# MCU.net
KiCad netlist of a schematic drawn in Altium Designer
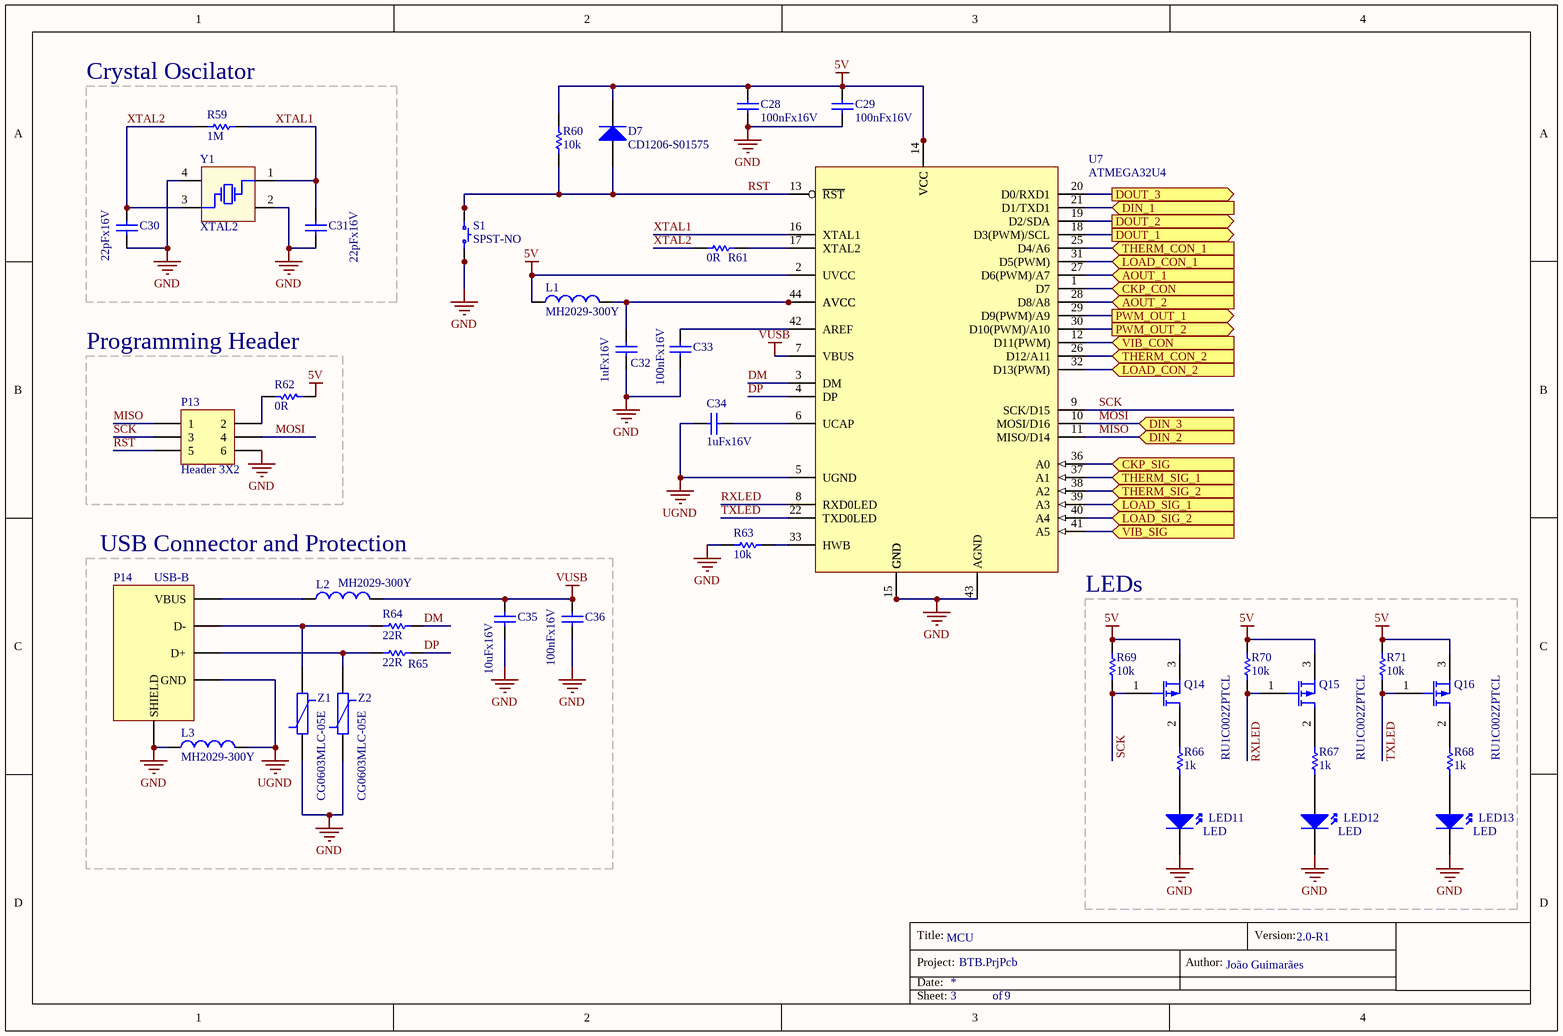
[diagram p0: MCU.SchDoc]

(export (version "E")
  (design (tool "Eeschema 10.0.6"))
  (components
    (comp (ref "C28")
      (value "100nFx16V")
      (footprint "DISC-0805")
      (description "Capacitor")
      (libsource (lib "IntLib") (part "Cap"))
    )
    (comp (ref "C29")
      (value "100nFx16V")
      (footprint "DISC-0805")
      (description "Capacitor")
      (libsource (lib "IntLib") (part "Cap"))
    )
    (comp (ref "C30")
      (value "22pFx16V")
      (footprint "DISC-0805")
      (description "Capacitor")
      (libsource (lib "IntLib") (part "Cap"))
    )
    (comp (ref "C31")
      (value "22pFx16V")
      (footprint "DISC-0805")
      (description "Capacitor")
      (libsource (lib "IntLib") (part "Cap"))
    )
    (comp (ref "C32")
      (value "1uFx16V")
      (footprint "DISC-0805")
      (description "Capacitor")
      (libsource (lib "IntLib") (part "Cap"))
    )
    (comp (ref "C33")
      (value "100nFx16V")
      (footprint "DISC-0805")
      (description "Capacitor")
      (libsource (lib "IntLib") (part "Cap"))
    )
    (comp (ref "C34")
      (value "1uFx16V")
      (footprint "DISC-0805")
      (description "Capacitor")
      (libsource (lib "IntLib") (part "Cap"))
    )
    (comp (ref "C35")
      (value "10uFx16V")
      (footprint "DISC-0805")
      (description "Capacitor")
      (libsource (lib "IntLib") (part "Cap"))
    )
    (comp (ref "C36")
      (value "100nFx16V")
      (footprint "DISC-0805")
      (description "Capacitor")
      (libsource (lib "IntLib") (part "Cap"))
    )
    (comp (ref "D7")
      (value "CD1206-S01575")
      (footprint "DISC-1206")
      (description "Default Diode")
      (fields (field (name "PUBLISHER") "Altium Limited"))
      (libsource (lib "IntLib") (part "Diode"))
    )
    (comp (ref "L1")
      (value "MH2029-300Y")
      (footprint "DISC-0805")
      (description "Chip Inductor")
      (libsource (lib "IntLib") (part "Inductor"))
    )
    (comp (ref "L2")
      (value "MH2029-300Y")
      (footprint "DISC-0805")
      (description "Chip Inductor")
      (libsource (lib "IntLib") (part "Inductor"))
    )
    (comp (ref "L3")
      (value "MH2029-300Y")
      (footprint "DISC-0805")
      (description "Chip Inductor")
      (libsource (lib "IntLib") (part "Inductor"))
    )
    (comp (ref "LED11") (value "LED") (footprint "DISC-LED-0.1-PTH") (libsource (lib "IntLib") (part "LED")))
    (comp (ref "LED12") (value "LED") (footprint "DISC-LED-0.1-PTH") (libsource (lib "IntLib") (part "LED")))
    (comp (ref "LED13") (value "LED") (footprint "DISC-LED-0.1-PTH") (libsource (lib "IntLib") (part "LED")))
    (comp (ref "P13")
      (value "Header 3X2")
      (footprint "CON-HEADER-2X3-PTH")
      (description "Header, 3-Pin, Dual row")
      (fields (field (name "PUBLISHER") "Altium Limited"))
      (libsource (lib "IntLib") (part "Header 3X2"))
    )
    (comp (ref "P14")
      (value "USB-B")
      (footprint "CON-USB-B")
      (description "USB Type-B")
      (libsource (lib "IntLib") (part "USB Type-B"))
    )
    (comp (ref "Q14")
      (value "RU1C002ZPTCL")
      (footprint "DISC-SOT-23")
      (description "P-Channel MOSFET")
      (libsource (lib "IntLib") (part "Transistor-PMOS"))
    )
    (comp (ref "Q15")
      (value "RU1C002ZPTCL")
      (footprint "DISC-SOT-23")
      (description "P-Channel MOSFET")
      (libsource (lib "IntLib") (part "Transistor-PMOS"))
    )
    (comp (ref "Q16")
      (value "RU1C002ZPTCL")
      (footprint "DISC-SOT-23")
      (description "P-Channel MOSFET")
      (libsource (lib "IntLib") (part "Transistor-PMOS"))
    )
    (comp (ref "R59")
      (value "1M")
      (footprint "DISC-0805")
      (description "Resistor")
      (libsource (lib "IntLib") (part "Res"))
    )
    (comp (ref "R60")
      (value "10k")
      (footprint "DISC-0805")
      (description "Resistor")
      (libsource (lib "IntLib") (part "Res"))
    )
    (comp (ref "R61")
      (value "0R")
      (footprint "DISC-0805")
      (description "Resistor")
      (libsource (lib "IntLib") (part "Res"))
    )
    (comp (ref "R62")
      (value "0R")
      (footprint "DISC-0805")
      (description "Resistor")
      (libsource (lib "IntLib") (part "Res"))
    )
    (comp (ref "R63")
      (value "10k")
      (footprint "DISC-0805")
      (description "Resistor")
      (libsource (lib "IntLib") (part "Res"))
    )
    (comp (ref "R64")
      (value "22R")
      (footprint "DISC-0805")
      (description "Resistor")
      (libsource (lib "IntLib") (part "Res"))
    )
    (comp (ref "R65")
      (value "22R")
      (footprint "DISC-0805")
      (description "Resistor")
      (libsource (lib "IntLib") (part "Res"))
    )
    (comp (ref "R66")
      (value "1k")
      (footprint "DISC-0805")
      (description "Resistor")
      (libsource (lib "IntLib") (part "Res"))
    )
    (comp (ref "R67")
      (value "1k")
      (footprint "DISC-0805")
      (description "Resistor")
      (libsource (lib "IntLib") (part "Res"))
    )
    (comp (ref "R68")
      (value "1k")
      (footprint "DISC-0805")
      (description "Resistor")
      (libsource (lib "IntLib") (part "Res"))
    )
    (comp (ref "R69")
      (value "10k")
      (footprint "DISC-0805")
      (description "Resistor")
      (libsource (lib "IntLib") (part "Res"))
    )
    (comp (ref "R70")
      (value "10k")
      (footprint "DISC-0805")
      (description "Resistor")
      (libsource (lib "IntLib") (part "Res"))
    )
    (comp (ref "R71")
      (value "10k")
      (footprint "DISC-0805")
      (description "Resistor")
      (libsource (lib "IntLib") (part "Res"))
    )
    (comp (ref "S1")
      (value "SPST-NO")
      (footprint "DISC-PUSHBUTTON-4P-SMD")
      (libsource (lib "IntLib") (part "SPST-NO"))
    )
    (comp (ref "U7")
      (value "ATMEGA32U4")
      (footprint "CI-QFP-44")
      (description "8-bit Microcontroller with 16/32K bytes of ISP Flash and  USB Controller")
      (libsource (lib "IntLib") (part "ATMEGA32U4-AU"))
    )
    (comp (ref "Y1")
      (value "XTAL2")
      (footprint "DISC-CRYSTAL-4P-3.2X2.5")
      (description "XTAL-4-PIN")
      (libsource (lib "IntLib") (part "XTAL-4-PIN"))
    )
    (comp (ref "Z1")
      (value "CG0603MLC-05E")
      (footprint "DISC-0603")
      (description "Varistor")
      (libsource (lib "IntLib") (part "Varistor"))
    )
    (comp (ref "Z2")
      (value "CG0603MLC-05E")
      (footprint "DISC-0603")
      (description "Varistor")
      (libsource (lib "IntLib") (part "Varistor"))
    )
  )
  (nets
    (net (code "1") (name "/AOUT_1") (class "Default")
      (node (ref "U7") (pin "27") (pinfunction "D6(PWM)/A7_27") (pintype "passive"))
    )
    (net (code "2") (name "/AOUT_2") (class "Default")
      (node (ref "U7") (pin "28") (pinfunction "D8/A8_28") (pintype "passive"))
    )
    (net (code "3") (name "/CKP_CON") (class "Default")
      (node (ref "U7") (pin "1") (pinfunction "D7_1") (pintype "passive"))
    )
    (net (code "4") (name "/CKP_SIG") (class "Default")
      (node (ref "U7") (pin "36") (pinfunction "A0_36") (pintype "input"))
    )
    (net (code "5") (name "/DIN_1") (class "Default")
      (node (ref "U7") (pin "21") (pinfunction "D1/TXD1_21") (pintype "passive"))
    )
    (net (code "6") (name "/DM") (class "Default")
      (node (ref "R64") (pin "2") (pinfunction "2_2") (pintype "passive"))
      (node (ref "U7") (pin "3") (pinfunction "DM_3") (pintype "passive"))
    )
    (net (code "7") (name "/DOUT_1") (class "Default")
      (node (ref "U7") (pin "18") (pinfunction "D3(PWM)/SCL_18") (pintype "passive"))
    )
    (net (code "8") (name "/DOUT_2") (class "Default")
      (node (ref "U7") (pin "19") (pinfunction "D2/SDA_19") (pintype "passive"))
    )
    (net (code "9") (name "/DOUT_3") (class "Default")
      (node (ref "U7") (pin "20") (pinfunction "D0/RXD1_20") (pintype "passive"))
    )
    (net (code "10") (name "/DP") (class "Default")
      (node (ref "R65") (pin "2") (pinfunction "2_2") (pintype "passive"))
      (node (ref "U7") (pin "4") (pinfunction "DP_4") (pintype "passive"))
    )
    (net (code "11") (name "/LOAD_CON_1") (class "Default")
      (node (ref "U7") (pin "31") (pinfunction "D5(PWM)_31") (pintype "passive"))
    )
    (net (code "12") (name "/LOAD_CON_2") (class "Default")
      (node (ref "U7") (pin "32") (pinfunction "D13(PWM)_32") (pintype "passive"))
    )
    (net (code "13") (name "/LOAD_SIG_1") (class "Default")
      (node (ref "U7") (pin "39") (pinfunction "A3_39") (pintype "input"))
    )
    (net (code "14") (name "/LOAD_SIG_2") (class "Default")
      (node (ref "U7") (pin "40") (pinfunction "A4_40") (pintype "input"))
    )
    (net (code "15") (name "/MISO") (class "Default")
      (node (ref "P13") (pin "1") (pinfunction "1_1") (pintype "passive"))
      (node (ref "U7") (pin "11") (pinfunction "MISO/D14_11") (pintype "passive"))
    )
    (net (code "16") (name "/MOSI") (class "Default")
      (node (ref "P13") (pin "4") (pinfunction "4_4") (pintype "passive"))
      (node (ref "U7") (pin "10") (pinfunction "MOSI/D16_10") (pintype "passive"))
    )
    (net (code "17") (name "/PWM_OUT_1") (class "Default")
      (node (ref "U7") (pin "29") (pinfunction "D9(PWM)/A9_29") (pintype "passive"))
    )
    (net (code "18") (name "/PWM_OUT_2") (class "Default")
      (node (ref "U7") (pin "30") (pinfunction "D10(PWM)/A10_30") (pintype "passive"))
    )
    (net (code "19") (name "/RST") (class "Default")
      (node (ref "D7") (pin "1") (pinfunction "A_1") (pintype "passive"))
      (node (ref "P13") (pin "5") (pinfunction "5_5") (pintype "passive"))
      (node (ref "R60") (pin "2") (pinfunction "2_2") (pintype "passive"))
      (node (ref "S1") (pin "3") (pinfunction "3_3") (pintype "passive"))
      (node (ref "S1") (pin "4") (pinfunction "4_4") (pintype "passive"))
      (node (ref "U7") (pin "13") (pinfunction "~{RST}_13") (pintype "passive"))
    )
    (net (code "20") (name "/RXLED") (class "Default")
      (node (ref "Q15") (pin "1") (pinfunction "G_1") (pintype "passive"))
      (node (ref "R70") (pin "2") (pinfunction "2_2") (pintype "passive"))
      (node (ref "U7") (pin "8") (pinfunction "RXD0LED_8") (pintype "passive"))
    )
    (net (code "21") (name "/SCK") (class "Default")
      (node (ref "P13") (pin "3") (pinfunction "3_3") (pintype "passive"))
      (node (ref "Q14") (pin "1") (pinfunction "G_1") (pintype "passive"))
      (node (ref "R69") (pin "2") (pinfunction "2_2") (pintype "passive"))
      (node (ref "U7") (pin "9") (pinfunction "SCK/D15_9") (pintype "passive"))
    )
    (net (code "22") (name "/THERM_CON_1") (class "Default")
      (node (ref "U7") (pin "25") (pinfunction "D4/A6_25") (pintype "passive"))
    )
    (net (code "23") (name "/THERM_CON_2") (class "Default")
      (node (ref "U7") (pin "26") (pinfunction "D12/A11_26") (pintype "passive"))
    )
    (net (code "24") (name "/THERM_SIG_1") (class "Default")
      (node (ref "U7") (pin "37") (pinfunction "A1_37") (pintype "input"))
    )
    (net (code "25") (name "/THERM_SIG_2") (class "Default")
      (node (ref "U7") (pin "38") (pinfunction "A2_38") (pintype "input"))
    )
    (net (code "26") (name "/TXLED") (class "Default")
      (node (ref "Q16") (pin "1") (pinfunction "G_1") (pintype "passive"))
      (node (ref "R71") (pin "2") (pinfunction "2_2") (pintype "passive"))
      (node (ref "U7") (pin "22") (pinfunction "TXD0LED_22") (pintype "passive"))
    )
    (net (code "27") (name "/VIB_CON") (class "Default")
      (node (ref "U7") (pin "12") (pinfunction "D11(PWM)_12") (pintype "passive"))
    )
    (net (code "28") (name "/VIB_SIG") (class "Default")
      (node (ref "U7") (pin "41") (pinfunction "A5_41") (pintype "input"))
    )
    (net (code "29") (name "/XTAL1") (class "Default")
      (node (ref "C31") (pin "2") (pinfunction "2_2") (pintype "passive"))
      (node (ref "R59") (pin "2") (pinfunction "2_2") (pintype "passive"))
      (node (ref "U7") (pin "16") (pinfunction "XTAL1_16") (pintype "passive"))
      (node (ref "Y1") (pin "1") (pinfunction "OSC1_1") (pintype "passive"))
    )
    (net (code "30") (name "/XTAL2") (class "Default")
      (node (ref "C30") (pin "2") (pinfunction "2_2") (pintype "passive"))
      (node (ref "R59") (pin "1") (pinfunction "1_1") (pintype "passive"))
      (node (ref "R61") (pin "1") (pinfunction "1_1") (pintype "passive"))
      (node (ref "Y1") (pin "3") (pinfunction "OSC2_3") (pintype "passive"))
    )
    (net (code "31") (name "5V") (class "Default")
      (node (ref "C28") (pin "1") (pinfunction "1_1") (pintype "passive"))
      (node (ref "C29") (pin "1") (pinfunction "1_1") (pintype "passive"))
      (node (ref "D7") (pin "2") (pinfunction "K_2") (pintype "passive"))
      (node (ref "L1") (pin "1") (pinfunction "1_1") (pintype "passive"))
      (node (ref "Q14") (pin "3") (pinfunction "S_3") (pintype "passive"))
      (node (ref "Q15") (pin "3") (pinfunction "S_3") (pintype "passive"))
      (node (ref "Q16") (pin "3") (pinfunction "S_3") (pintype "passive"))
      (node (ref "R60") (pin "1") (pinfunction "1_1") (pintype "passive"))
      (node (ref "R62") (pin "2") (pinfunction "2_2") (pintype "passive"))
      (node (ref "R69") (pin "1") (pinfunction "1_1") (pintype "passive"))
      (node (ref "R70") (pin "1") (pinfunction "1_1") (pintype "passive"))
      (node (ref "R71") (pin "1") (pinfunction "1_1") (pintype "passive"))
      (node (ref "U7") (pin "14") (pinfunction "VCC_14") (pintype "power_in"))
      (node (ref "U7") (pin "2") (pinfunction "UVCC_2") (pintype "power_in"))
      (node (ref "U7") (pin "34") (pinfunction "VCC_34") (pintype "power_in"))
    )
    (net (code "32") (name "GND") (class "Default")
      (node (ref "C28") (pin "2") (pinfunction "2_2") (pintype "passive"))
      (node (ref "C29") (pin "2") (pinfunction "2_2") (pintype "passive"))
      (node (ref "C30") (pin "1") (pinfunction "1_1") (pintype "passive"))
      (node (ref "C31") (pin "1") (pinfunction "1_1") (pintype "passive"))
      (node (ref "C32") (pin "2") (pinfunction "2_2") (pintype "passive"))
      (node (ref "C33") (pin "2") (pinfunction "2_2") (pintype "passive"))
      (node (ref "C35") (pin "2") (pinfunction "2_2") (pintype "passive"))
      (node (ref "C36") (pin "2") (pinfunction "2_2") (pintype "passive"))
      (node (ref "L3") (pin "1") (pinfunction "1_1") (pintype "passive"))
      (node (ref "LED11") (pin "2") (pinfunction "K_2") (pintype "passive"))
      (node (ref "LED12") (pin "2") (pinfunction "K_2") (pintype "passive"))
      (node (ref "LED13") (pin "2") (pinfunction "K_2") (pintype "passive"))
      (node (ref "P13") (pin "6") (pinfunction "6_6") (pintype "passive"))
      (node (ref "P14") (pin "5") (pinfunction "SHIELD_5") (pintype "passive"))
      (node (ref "P14") (pin "6") (pinfunction "SHIELD_6") (pintype "passive"))
      (node (ref "R63") (pin "1") (pinfunction "1_1") (pintype "passive"))
      (node (ref "S1") (pin "1") (pinfunction "1_1") (pintype "passive"))
      (node (ref "S1") (pin "2") (pinfunction "2_2") (pintype "passive"))
      (node (ref "U7") (pin "15") (pinfunction "GND_15") (pintype "power_in"))
      (node (ref "U7") (pin "23") (pinfunction "GND_23") (pintype "power_in"))
      (node (ref "U7") (pin "35") (pinfunction "GND_35") (pintype "power_in"))
      (node (ref "U7") (pin "43") (pinfunction "AGND_43") (pintype "power_in"))
      (node (ref "Y1") (pin "2") (pinfunction "GND_2") (pintype "passive"))
      (node (ref "Y1") (pin "4") (pinfunction "GND_4") (pintype "passive"))
      (node (ref "Z1") (pin "1") (pinfunction "1_1") (pintype "passive"))
      (node (ref "Z2") (pin "1") (pinfunction "1_1") (pintype "passive"))
    )
    (net (code "33") (name "Net-(C32-Pad1)") (class "Default")
      (node (ref "C32") (pin "1") (pinfunction "1_1") (pintype "passive"))
      (node (ref "L1") (pin "2") (pinfunction "2_2") (pintype "passive"))
      (node (ref "U7") (pin "24") (pinfunction "AVCC_24") (pintype "power_in"))
      (node (ref "U7") (pin "44") (pinfunction "AVCC_44") (pintype "power_in"))
    )
    (net (code "34") (name "Net-(LED11-A)") (class "Default")
      (node (ref "LED11") (pin "1") (pinfunction "A_1") (pintype "passive"))
      (node (ref "R66") (pin "2") (pinfunction "2_2") (pintype "passive"))
    )
    (net (code "35") (name "Net-(LED12-A)") (class "Default")
      (node (ref "LED12") (pin "1") (pinfunction "A_1") (pintype "passive"))
      (node (ref "R67") (pin "2") (pinfunction "2_2") (pintype "passive"))
    )
    (net (code "36") (name "Net-(LED13-A)") (class "Default")
      (node (ref "LED13") (pin "1") (pinfunction "A_1") (pintype "passive"))
      (node (ref "R68") (pin "2") (pinfunction "2_2") (pintype "passive"))
    )
    (net (code "37") (name "Net-(P13-Pad2)") (class "Default")
      (node (ref "P13") (pin "2") (pinfunction "2_2") (pintype "passive"))
      (node (ref "R62") (pin "1") (pinfunction "1_1") (pintype "passive"))
    )
    (net (code "38") (name "Net-(P14-D+)") (class "Default")
      (node (ref "P14") (pin "3") (pinfunction "D+_3") (pintype "passive"))
      (node (ref "R65") (pin "1") (pinfunction "1_1") (pintype "passive"))
      (node (ref "Z2") (pin "2") (pinfunction "2_2") (pintype "passive"))
    )
    (net (code "39") (name "Net-(P14-D-)") (class "Default")
      (node (ref "P14") (pin "2") (pinfunction "D-_2") (pintype "passive"))
      (node (ref "R64") (pin "1") (pinfunction "1_1") (pintype "passive"))
      (node (ref "Z1") (pin "2") (pinfunction "2_2") (pintype "passive"))
    )
    (net (code "40") (name "Net-(P14-VBUS)") (class "Default")
      (node (ref "L2") (pin "1") (pinfunction "1_1") (pintype "passive"))
      (node (ref "P14") (pin "1") (pinfunction "VBUS_1") (pintype "passive"))
    )
    (net (code "41") (name "Net-(Q14-D)") (class "Default")
      (node (ref "Q14") (pin "2") (pinfunction "D_2") (pintype "passive"))
      (node (ref "R66") (pin "1") (pinfunction "1_1") (pintype "passive"))
    )
    (net (code "42") (name "Net-(Q15-D)") (class "Default")
      (node (ref "Q15") (pin "2") (pinfunction "D_2") (pintype "passive"))
      (node (ref "R67") (pin "1") (pinfunction "1_1") (pintype "passive"))
    )
    (net (code "43") (name "Net-(Q16-D)") (class "Default")
      (node (ref "Q16") (pin "2") (pinfunction "D_2") (pintype "passive"))
      (node (ref "R68") (pin "1") (pinfunction "1_1") (pintype "passive"))
    )
    (net (code "44") (name "Net-(U7-AREF)") (class "Default")
      (node (ref "C33") (pin "1") (pinfunction "1_1") (pintype "passive"))
      (node (ref "U7") (pin "42") (pinfunction "AREF_42") (pintype "power_in"))
    )
    (net (code "45") (name "Net-(U7-HWB)") (class "Default")
      (node (ref "R63") (pin "2") (pinfunction "2_2") (pintype "passive"))
      (node (ref "U7") (pin "33") (pinfunction "HWB_33") (pintype "passive"))
    )
    (net (code "46") (name "Net-(U7-UCAP)") (class "Default")
      (node (ref "C34") (pin "2") (pinfunction "2_2") (pintype "passive"))
      (node (ref "U7") (pin "6") (pinfunction "UCAP_6") (pintype "power_in"))
    )
    (net (code "47") (name "Net-(U7-XTAL2)") (class "Default")
      (node (ref "R61") (pin "2") (pinfunction "2_2") (pintype "passive"))
      (node (ref "U7") (pin "17") (pinfunction "XTAL2_17") (pintype "passive"))
    )
    (net (code "48") (name "UGND") (class "Default")
      (node (ref "C34") (pin "1") (pinfunction "1_1") (pintype "passive"))
      (node (ref "L3") (pin "2") (pinfunction "2_2") (pintype "passive"))
      (node (ref "P14") (pin "4") (pinfunction "GND_4") (pintype "passive"))
      (node (ref "U7") (pin "5") (pinfunction "UGND_5") (pintype "power_in"))
    )
    (net (code "49") (name "VUSB") (class "Default")
      (node (ref "C35") (pin "1") (pinfunction "1_1") (pintype "passive"))
      (node (ref "C36") (pin "1") (pinfunction "1_1") (pintype "passive"))
      (node (ref "L2") (pin "2") (pinfunction "2_2") (pintype "passive"))
      (node (ref "U7") (pin "7") (pinfunction "VBUS_7") (pintype "power_in"))
    )
  )
)
